# 6c.net
KiCad netlist of a schematic drawn in EAGLE
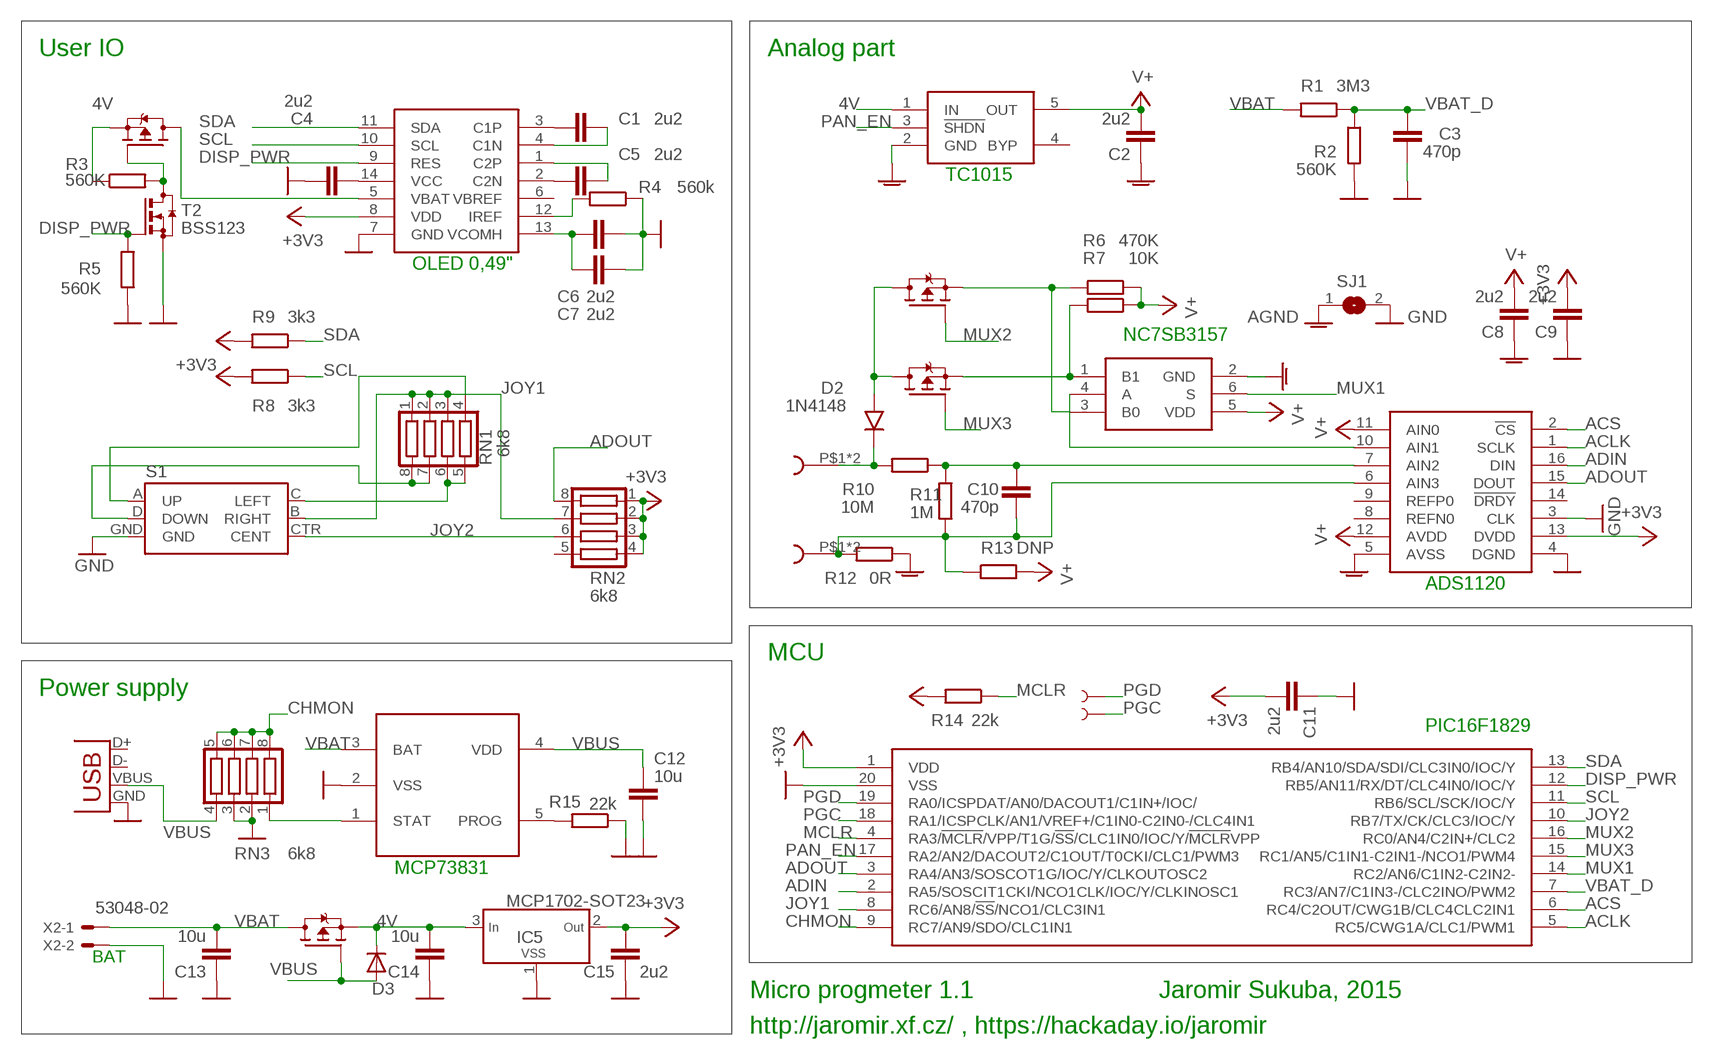
[diagram p0: schematic, sheet 1]

(export (version "E")
  (design (tool "Eeschema 10.0.6"))
  (components
    (comp (ref "C1")
      (value "2u2")
      (footprint "eagle-import:0603")
      (libsource (lib "eagle-import") (part "C_0603"))
    )
    (comp (ref "C2")
      (value "2u2")
      (footprint "eagle-import:0603")
      (libsource (lib "eagle-import") (part "C_0603"))
    )
    (comp (ref "C3")
      (value "470p")
      (footprint "eagle-import:0603")
      (libsource (lib "eagle-import") (part "C_0603"))
    )
    (comp (ref "C4")
      (value "2u2")
      (footprint "eagle-import:0603")
      (libsource (lib "eagle-import") (part "C_0603"))
    )
    (comp (ref "C5")
      (value "2u2")
      (footprint "eagle-import:0603")
      (libsource (lib "eagle-import") (part "C_0603"))
    )
    (comp (ref "C6")
      (value "2u2")
      (footprint "eagle-import:0603")
      (libsource (lib "eagle-import") (part "C_0603"))
    )
    (comp (ref "C7")
      (value "2u2")
      (footprint "eagle-import:0603")
      (libsource (lib "eagle-import") (part "C_0603"))
    )
    (comp (ref "C8")
      (value "2u2")
      (footprint "eagle-import:0603")
      (libsource (lib "eagle-import") (part "C_0603"))
    )
    (comp (ref "C9")
      (value "2u2")
      (footprint "eagle-import:0603")
      (libsource (lib "eagle-import") (part "C_0603"))
    )
    (comp (ref "C10")
      (value "470p")
      (footprint "eagle-import:0603")
      (libsource (lib "eagle-import") (part "C_0603"))
    )
    (comp (ref "C11")
      (value "2u2")
      (footprint "eagle-import:0603")
      (libsource (lib "eagle-import") (part "C_0603"))
    )
    (comp (ref "C12")
      (value "10u")
      (footprint "eagle-import:R0805")
      (libsource (lib "eagle-import") (part "C_0806"))
    )
    (comp (ref "C13")
      (value "10u")
      (footprint "eagle-import:R0805")
      (libsource (lib "eagle-import") (part "C_0806"))
    )
    (comp (ref "C14")
      (value "10u")
      (footprint "eagle-import:R0805")
      (libsource (lib "eagle-import") (part "C_0806"))
    )
    (comp (ref "C15")
      (value "2u2")
      (footprint "eagle-import:0603")
      (libsource (lib "eagle-import") (part "C_0603"))
    )
    (comp (ref "D1")
      (value "DISP_OLED_049B")
      (footprint "eagle-import:DISP_OLED_049_B")
      (libsource (lib "eagle-import") (part "DISP_OLED_049B"))
    )
    (comp (ref "D2")
      (value "1N4148")
      (footprint "eagle-import:SOD-80")
      (libsource (lib "eagle-import") (part "1N4148SOD"))
    )
    (comp (ref "D3")
      (value "DIODE-SOD123")
      (footprint "eagle-import:SOD123")
      (libsource (lib "eagle-import") (part "DIODE-SOD123"))
    )
    (comp (ref "IC1")
      (value "TC1015")
      (footprint "eagle-import:SOT23-5")
      (libsource (lib "eagle-import") (part "TC1015"))
    )
    (comp (ref "IC2")
      (value "NC7SB3157")
      (footprint "eagle-import:SC70-6")
      (libsource (lib "eagle-import") (part "NC7SB3157"))
    )
    (comp (ref "IC3")
      (value "ADS1120")
      (footprint "eagle-import:TSSOP16")
      (libsource (lib "eagle-import") (part "ADS1120"))
    )
    (comp (ref "IC4")
      (value "PIC16F1508SSOP20")
      (footprint "eagle-import:SSOP20")
      (libsource (lib "eagle-import") (part "PIC16F1508SSOP20"))
    )
    (comp (ref "IC5")
      (value "MCP1702-SOT23")
      (footprint "eagle-import:SOT23")
      (libsource (lib "eagle-import") (part "MCP1702-SOT23"))
    )
    (comp (ref "R1")
      (value "3M3")
      (footprint "eagle-import:0603")
      (libsource (lib "eagle-import") (part "R_0603"))
    )
    (comp (ref "R2")
      (value "560K")
      (footprint "eagle-import:0603")
      (libsource (lib "eagle-import") (part "R_0603"))
    )
    (comp (ref "R3")
      (value "560K")
      (footprint "eagle-import:0603")
      (libsource (lib "eagle-import") (part "R_0603"))
    )
    (comp (ref "R4")
      (value "560k")
      (footprint "eagle-import:0603")
      (libsource (lib "eagle-import") (part "R_0603"))
    )
    (comp (ref "R5")
      (value "560K")
      (footprint "eagle-import:0603")
      (libsource (lib "eagle-import") (part "R_0603"))
    )
    (comp (ref "R6")
      (value "470K")
      (footprint "eagle-import:R0805")
      (libsource (lib "eagle-import") (part "R_0805"))
    )
    (comp (ref "R7")
      (value "10K")
      (footprint "eagle-import:R0805")
      (libsource (lib "eagle-import") (part "R_0805"))
    )
    (comp (ref "R8")
      (value "3k3")
      (footprint "eagle-import:0603")
      (libsource (lib "eagle-import") (part "R_0603"))
    )
    (comp (ref "R9")
      (value "3k3")
      (footprint "eagle-import:0603")
      (libsource (lib "eagle-import") (part "R_0603"))
    )
    (comp (ref "R10")
      (value "10M")
      (footprint "eagle-import:R0805")
      (libsource (lib "eagle-import") (part "R_0805"))
    )
    (comp (ref "R11")
      (value "1M")
      (footprint "eagle-import:R0805")
      (libsource (lib "eagle-import") (part "R_0805"))
    )
    (comp (ref "R12")
      (value "0R")
      (footprint "eagle-import:0603")
      (libsource (lib "eagle-import") (part "R_0603"))
    )
    (comp (ref "R13")
      (value "DNP")
      (footprint "eagle-import:0603")
      (libsource (lib "eagle-import") (part "R_0603"))
    )
    (comp (ref "R14")
      (value "22k")
      (footprint "eagle-import:0603")
      (libsource (lib "eagle-import") (part "R_0603"))
    )
    (comp (ref "R15")
      (value "22k")
      (footprint "eagle-import:0603")
      (libsource (lib "eagle-import") (part "R_0603"))
    )
    (comp (ref "RN1")
      (value "6k8")
      (footprint "eagle-import:CTS742C083")
      (libsource (lib "eagle-import") (part "CTS742C083"))
    )
    (comp (ref "RN2")
      (value "6k8")
      (footprint "eagle-import:CTS742C083")
      (libsource (lib "eagle-import") (part "CTS742C083"))
    )
    (comp (ref "RN3")
      (value "6k8")
      (footprint "eagle-import:CTS742C083")
      (libsource (lib "eagle-import") (part "CTS742C083"))
    )
    (comp (ref "S1")
      (value "JOYSTICK_MINI")
      (footprint "eagle-import:JOYSTICK_MINI")
      (libsource (lib "eagle-import") (part "JOYSTICK_MINI"))
    )
    (comp (ref "SJ1") (value "SJ") (footprint "eagle-import:SJ") (libsource (lib "eagle-import") (part "SJ")))
    (comp (ref "T1")
      (value "BSS84")
      (footprint "eagle-import:SOT23-3")
      (libsource (lib "eagle-import") (part "BSS84"))
    )
    (comp (ref "T2")
      (value "BSS123")
      (footprint "eagle-import:SOT23")
      (libsource (lib "eagle-import") (part "BSS123"))
    )
    (comp (ref "T3")
      (value "BSS84")
      (footprint "eagle-import:SOT23-3")
      (libsource (lib "eagle-import") (part "BSS84"))
    )
    (comp (ref "T4")
      (value "BSS84")
      (footprint "eagle-import:SOT23-3")
      (libsource (lib "eagle-import") (part "BSS84"))
    )
    (comp (ref "T5")
      (value "BSS84")
      (footprint "eagle-import:SOT23-3")
      (libsource (lib "eagle-import") (part "BSS84"))
    )
    (comp (ref "TP1")
      (value "TEST-POINT3X5")
      (footprint "eagle-import:PAD.03X.05")
      (libsource (lib "eagle-import") (part "TEST-POINT3X5"))
    )
    (comp (ref "TP2")
      (value "TEST-POINT3X5")
      (footprint "eagle-import:PAD.03X.05")
      (libsource (lib "eagle-import") (part "TEST-POINT3X5"))
    )
    (comp (ref "U$1")
      (value "BANPLUG_2")
      (footprint "eagle-import:BANPLUG_2")
      (libsource (lib "eagle-import") (part "BANPLUG_2"))
    )
    (comp (ref "U$2")
      (value "BANPLUG_2")
      (footprint "eagle-import:BANPLUG_2")
      (libsource (lib "eagle-import") (part "BANPLUG_2"))
    )
    (comp (ref "U$3")
      (value "MCP73831")
      (footprint "eagle-import:SOT23-5")
      (libsource (lib "eagle-import") (part "MCP73831"))
    )
    (comp (ref "X1")
      (value "USB-MICROB")
      (footprint "eagle-import:USB-MICROB")
      (libsource (lib "eagle-import") (part "USB-MICROB"))
    )
    (comp (ref "X2")
      (value "53048-02")
      (footprint "eagle-import:53048-02")
      (libsource (lib "eagle-import") (part "53?-02048"))
    )
  )
  (nets
    (net (code "1") (name "+3V3") (class "Default")
      (node (ref "C11") (pin "2") (pinfunction "2_2") (pintype "passive"))
      (node (ref "C15") (pin "2") (pinfunction "2_2") (pintype "passive"))
      (node (ref "C9") (pin "2") (pinfunction "2_2") (pintype "passive"))
      (node (ref "D1") (pin "8") (pinfunction "VDD_8") (pintype "bidirectional"))
      (node (ref "IC3") (pin "13") (pinfunction "DVDD_13") (pintype "bidirectional"))
      (node (ref "IC4") (pin "1") (pinfunction "VDD_1") (pintype "bidirectional"))
      (node (ref "IC5") (pin "2") (pinfunction "OUT_2") (pintype "output"))
      (node (ref "R14") (pin "2") (pinfunction "2_2") (pintype "passive"))
      (node (ref "R8") (pin "2") (pinfunction "2_2") (pintype "passive"))
      (node (ref "R9") (pin "2") (pinfunction "2_2") (pintype "passive"))
      (node (ref "RN2") (pin "1") (pinfunction "1_1") (pintype "passive"))
      (node (ref "RN2") (pin "2") (pinfunction "2_2") (pintype "passive"))
      (node (ref "RN2") (pin "3") (pinfunction "3_3") (pintype "passive"))
      (node (ref "RN2") (pin "4") (pinfunction "4_4") (pintype "passive"))
    )
    (net (code "2") (name "/4V") (class "Default")
      (node (ref "C14") (pin "2") (pinfunction "2_2") (pintype "passive"))
      (node (ref "D3") (pin "C") (pinfunction "C_C") (pintype "passive"))
      (node (ref "IC1") (pin "1") (pinfunction "IN_1") (pintype "bidirectional"))
      (node (ref "IC5") (pin "3") (pinfunction "IN_3") (pintype "input"))
      (node (ref "R3") (pin "1") (pinfunction "1_1") (pintype "passive"))
      (node (ref "T1") (pin "2") (pinfunction "S_2") (pintype "passive"))
      (node (ref "T5") (pin "2") (pinfunction "S_2") (pintype "passive"))
    )
    (net (code "3") (name "/ACLK") (class "Default")
      (node (ref "IC3") (pin "1") (pinfunction "SCLK_1") (pintype "bidirectional"))
      (node (ref "IC4") (pin "5") (pinfunction "RC5/CWG1A/CLC1/PWM1_5") (pintype "bidirectional"))
    )
    (net (code "4") (name "/ACS") (class "Default")
      (node (ref "IC3") (pin "2") (pinfunction "~{CS}_2") (pintype "bidirectional"))
      (node (ref "IC4") (pin "6") (pinfunction "RC4/C2OUT/CWG1B/CLC4CLC2IN1_6") (pintype "bidirectional"))
    )
    (net (code "5") (name "/ADIN") (class "Default")
      (node (ref "IC3") (pin "16") (pinfunction "DIN_16") (pintype "bidirectional"))
      (node (ref "IC4") (pin "2") (pinfunction "RA5/SOSCIT1CKI/NCO1CLK/IOC/Y/CLKINOSC1_2") (pintype "bidirectional"))
    )
    (net (code "6") (name "/ADOUT") (class "Default")
      (node (ref "IC3") (pin "15") (pinfunction "DOUT_15") (pintype "bidirectional"))
      (node (ref "IC4") (pin "3") (pinfunction "RA4/AN3/SOSCOT1G/IOC/Y/CLKOUTOSC2_3") (pintype "bidirectional"))
      (node (ref "RN2") (pin "8") (pinfunction "8_8") (pintype "passive"))
    )
    (net (code "7") (name "/CHMON") (class "Default")
      (node (ref "IC4") (pin "9") (pinfunction "RC7/AN9/SDO/CLC1IN1_9") (pintype "bidirectional"))
      (node (ref "RN3") (pin "5") (pinfunction "5_5") (pintype "passive"))
      (node (ref "RN3") (pin "6") (pinfunction "6_6") (pintype "passive"))
      (node (ref "RN3") (pin "7") (pinfunction "7_7") (pintype "passive"))
      (node (ref "RN3") (pin "8") (pinfunction "8_8") (pintype "passive"))
    )
    (net (code "8") (name "/DISP_PWR") (class "Default")
      (node (ref "D1") (pin "9") (pinfunction "RES_9") (pintype "bidirectional"))
      (node (ref "IC4") (pin "12") (pinfunction "RB5/AN11/RX/DT/CLC4IN0/IOC/Y_12") (pintype "bidirectional"))
      (node (ref "R5") (pin "2") (pinfunction "2_2") (pintype "passive"))
      (node (ref "T2") (pin "1") (pinfunction "G_1") (pintype "passive"))
    )
    (net (code "9") (name "/JOY1") (class "Default")
      (node (ref "IC4") (pin "8") (pinfunction "RC6/AN8/~{SS}/NCO1/CLC3IN1_8") (pintype "bidirectional"))
      (node (ref "RN1") (pin "1") (pinfunction "1_1") (pintype "passive"))
      (node (ref "RN1") (pin "2") (pinfunction "2_2") (pintype "passive"))
      (node (ref "RN1") (pin "3") (pinfunction "3_3") (pintype "passive"))
      (node (ref "RN2") (pin "7") (pinfunction "7_7") (pintype "passive"))
      (node (ref "S1") (pin "B") (pinfunction "RIGHT_B") (pintype "bidirectional"))
    )
    (net (code "10") (name "/JOY2") (class "Default")
      (node (ref "IC4") (pin "10") (pinfunction "RB7/TX/CK/CLC3/IOC/Y_10") (pintype "bidirectional"))
      (node (ref "RN2") (pin "6") (pinfunction "6_6") (pintype "passive"))
      (node (ref "S1") (pin "CTR") (pinfunction "CENT_CTR") (pintype "bidirectional"))
    )
    (net (code "11") (name "/MCLR") (class "Default")
      (node (ref "IC4") (pin "4") (pinfunction "RA3/~{MCLR}/VPP/T1G/~{SS}/CLC1IN0/IOC/Y/~{MCLR}VPP_4") (pintype "bidirectional"))
      (node (ref "R14") (pin "1") (pinfunction "1_1") (pintype "passive"))
    )
    (net (code "12") (name "/MUX1") (class "Default")
      (node (ref "IC2") (pin "6") (pinfunction "S_6") (pintype "bidirectional"))
      (node (ref "IC4") (pin "14") (pinfunction "RC2/AN6/C1IN2-C2IN2-_14") (pintype "bidirectional"))
    )
    (net (code "13") (name "/MUX2") (class "Default")
      (node (ref "IC4") (pin "16") (pinfunction "RC0/AN4/C2IN+/CLC2_16") (pintype "bidirectional"))
      (node (ref "T3") (pin "1") (pinfunction "G_1") (pintype "passive"))
    )
    (net (code "14") (name "/MUX3") (class "Default")
      (node (ref "IC4") (pin "15") (pinfunction "RC1/AN5/C1IN1-C2IN1-/NCO1/PWM4_15") (pintype "bidirectional"))
      (node (ref "T4") (pin "1") (pinfunction "G_1") (pintype "passive"))
    )
    (net (code "15") (name "/PAN_EN") (class "Default")
      (node (ref "IC1") (pin "3") (pinfunction "~{SHDN}_3") (pintype "bidirectional"))
      (node (ref "IC4") (pin "17") (pinfunction "RA2/AN2/DACOUT2/C1OUT/T0CKI/CLC1/PWM3_17") (pintype "bidirectional"))
    )
    (net (code "16") (name "/PGC") (class "Default")
      (node (ref "IC4") (pin "18") (pinfunction "RA1/ICSPCLK/AN1/VREF+/C1IN0-C2IN0-/CLC4IN1_18") (pintype "bidirectional"))
      (node (ref "TP2") (pin "P$1") (pinfunction "1_P$1") (pintype "bidirectional"))
    )
    (net (code "17") (name "/PGD") (class "Default")
      (node (ref "IC4") (pin "19") (pinfunction "RA0/ICSPDAT/AN0/DACOUT1/C1IN+/IOC/_19") (pintype "bidirectional"))
      (node (ref "TP1") (pin "P$1") (pinfunction "1_P$1") (pintype "bidirectional"))
    )
    (net (code "18") (name "/SCL") (class "Default")
      (node (ref "D1") (pin "10") (pinfunction "SCL_10") (pintype "bidirectional"))
      (node (ref "IC4") (pin "11") (pinfunction "RB6/SCL/SCK/IOC/Y_11") (pintype "bidirectional"))
      (node (ref "R9") (pin "1") (pinfunction "1_1") (pintype "passive"))
    )
    (net (code "19") (name "/SDA") (class "Default")
      (node (ref "D1") (pin "11") (pinfunction "SDA_11") (pintype "bidirectional"))
      (node (ref "IC4") (pin "13") (pinfunction "RB4/AN10/SDA/SDI/CLC3IN0/IOC/Y_13") (pintype "bidirectional"))
      (node (ref "R8") (pin "1") (pinfunction "1_1") (pintype "passive"))
    )
    (net (code "20") (name "/VBAT") (class "Default")
      (node (ref "C13") (pin "2") (pinfunction "2_2") (pintype "passive"))
      (node (ref "R1") (pin "2") (pinfunction "2_2") (pintype "passive"))
      (node (ref "T5") (pin "3") (pinfunction "D_3") (pintype "passive"))
      (node (ref "U$3") (pin "3") (pinfunction "BAT_3") (pintype "bidirectional"))
      (node (ref "X2") (pin "1") (pinfunction "S_1") (pintype "passive"))
    )
    (net (code "21") (name "/VBAT_D") (class "Default")
      (node (ref "C3") (pin "2") (pinfunction "2_2") (pintype "passive"))
      (node (ref "IC4") (pin "7") (pinfunction "RC3/AN7/C1IN3-/CLC2INO/PWM2_7") (pintype "bidirectional"))
      (node (ref "R1") (pin "1") (pinfunction "1_1") (pintype "passive"))
      (node (ref "R2") (pin "1") (pinfunction "1_1") (pintype "passive"))
    )
    (net (code "22") (name "/VBUS") (class "Default")
      (node (ref "C12") (pin "1") (pinfunction "1_1") (pintype "passive"))
      (node (ref "D3") (pin "A") (pinfunction "A_A") (pintype "passive"))
      (node (ref "RN3") (pin "4") (pinfunction "4_4") (pintype "passive"))
      (node (ref "T5") (pin "1") (pinfunction "G_1") (pintype "passive"))
      (node (ref "U$3") (pin "4") (pinfunction "VDD_4") (pintype "bidirectional"))
      (node (ref "X1") (pin "VBUS") (pinfunction "VBUS_VBUS") (pintype "bidirectional"))
    )
    (net (code "23") (name "AGND") (class "Default")
      (node (ref "C2") (pin "1") (pinfunction "1_1") (pintype "passive"))
      (node (ref "C8") (pin "1") (pinfunction "1_1") (pintype "passive"))
      (node (ref "IC1") (pin "2") (pinfunction "GND_2") (pintype "bidirectional"))
      (node (ref "IC2") (pin "2") (pinfunction "GND_2") (pintype "bidirectional"))
      (node (ref "IC3") (pin "5") (pinfunction "AVSS_5") (pintype "bidirectional"))
      (node (ref "R12") (pin "1") (pinfunction "1_1") (pintype "passive"))
      (node (ref "SJ1") (pin "1") (pinfunction "1_1") (pintype "passive"))
    )
    (net (code "24") (name "GND") (class "Default")
      (node (ref "C11") (pin "1") (pinfunction "1_1") (pintype "passive"))
      (node (ref "C12") (pin "2") (pinfunction "2_2") (pintype "passive"))
      (node (ref "C13") (pin "1") (pinfunction "1_1") (pintype "passive"))
      (node (ref "C14") (pin "1") (pinfunction "1_1") (pintype "passive"))
      (node (ref "C15") (pin "1") (pinfunction "1_1") (pintype "passive"))
      (node (ref "C3") (pin "1") (pinfunction "1_1") (pintype "passive"))
      (node (ref "C4") (pin "1") (pinfunction "1_1") (pintype "passive"))
      (node (ref "C6") (pin "2") (pinfunction "2_2") (pintype "passive"))
      (node (ref "C7") (pin "2") (pinfunction "2_2") (pintype "passive"))
      (node (ref "C9") (pin "1") (pinfunction "1_1") (pintype "passive"))
      (node (ref "D1") (pin "7") (pinfunction "GND_7") (pintype "bidirectional"))
      (node (ref "IC3") (pin "3") (pinfunction "CLK_3") (pintype "bidirectional"))
      (node (ref "IC3") (pin "4") (pinfunction "DGND_4") (pintype "bidirectional"))
      (node (ref "IC4") (pin "20") (pinfunction "VSS_20") (pintype "bidirectional"))
      (node (ref "IC5") (pin "1") (pinfunction "VSS_1") (pintype "input"))
      (node (ref "R15") (pin "1") (pinfunction "1_1") (pintype "passive"))
      (node (ref "R2") (pin "2") (pinfunction "2_2") (pintype "passive"))
      (node (ref "R4") (pin "1") (pinfunction "1_1") (pintype "passive"))
      (node (ref "R5") (pin "1") (pinfunction "1_1") (pintype "passive"))
      (node (ref "RN3") (pin "2") (pinfunction "2_2") (pintype "passive"))
      (node (ref "RN3") (pin "3") (pinfunction "3_3") (pintype "passive"))
      (node (ref "S1") (pin "GND") (pinfunction "GND_GND") (pintype "bidirectional"))
      (node (ref "SJ1") (pin "2") (pinfunction "2_2") (pintype "passive"))
      (node (ref "T2") (pin "2") (pinfunction "S_2") (pintype "passive"))
      (node (ref "U$3") (pin "2") (pinfunction "VSS_2") (pintype "bidirectional"))
      (node (ref "X1") (pin "GND") (pinfunction "GND_GND") (pintype "bidirectional"))
      (node (ref "X2") (pin "2") (pinfunction "S_2") (pintype "passive"))
    )
    (net (code "25") (name "Net-(D1-C1N)") (class "Default")
      (node (ref "C1") (pin "2") (pinfunction "2_2") (pintype "passive"))
      (node (ref "D1") (pin "4") (pinfunction "C1N_4") (pintype "bidirectional"))
    )
    (net (code "26") (name "Net-(D1-C1P)") (class "Default")
      (node (ref "C1") (pin "1") (pinfunction "1_1") (pintype "passive"))
      (node (ref "D1") (pin "3") (pinfunction "C1P_3") (pintype "bidirectional"))
    )
    (net (code "27") (name "Net-(D1-C2N)") (class "Default")
      (node (ref "C5") (pin "1") (pinfunction "1_1") (pintype "passive"))
      (node (ref "D1") (pin "2") (pinfunction "C2N_2") (pintype "bidirectional"))
    )
    (net (code "28") (name "Net-(D1-C2P)") (class "Default")
      (node (ref "C5") (pin "2") (pinfunction "2_2") (pintype "passive"))
      (node (ref "D1") (pin "1") (pinfunction "C2P_1") (pintype "bidirectional"))
    )
    (net (code "29") (name "Net-(D1-IREF)") (class "Default")
      (node (ref "D1") (pin "12") (pinfunction "IREF_12") (pintype "bidirectional"))
      (node (ref "R4") (pin "2") (pinfunction "2_2") (pintype "passive"))
    )
    (net (code "30") (name "Net-(D1-VBAT)") (class "Default")
      (node (ref "D1") (pin "5") (pinfunction "VBAT_5") (pintype "bidirectional"))
      (node (ref "T1") (pin "3") (pinfunction "D_3") (pintype "passive"))
    )
    (net (code "31") (name "Net-(D1-VCC)") (class "Default")
      (node (ref "C4") (pin "2") (pinfunction "2_2") (pintype "passive"))
      (node (ref "D1") (pin "14") (pinfunction "VCC_14") (pintype "bidirectional"))
    )
    (net (code "32") (name "Net-(D1-VCOMH)") (class "Default")
      (node (ref "C6") (pin "1") (pinfunction "1_1") (pintype "passive"))
      (node (ref "C7") (pin "1") (pinfunction "1_1") (pintype "passive"))
      (node (ref "D1") (pin "13") (pinfunction "VCOMH_13") (pintype "bidirectional"))
    )
    (net (code "33") (name "Net-(D2-PadK)") (class "Default")
      (node (ref "D2") (pin "K") (pinfunction "K_K") (pintype "output"))
      (node (ref "R10") (pin "2") (pinfunction "2_2") (pintype "passive"))
      (node (ref "U$1") (pin "P$1") (pinfunction "P$1_P$1") (pintype "bidirectional"))
      (node (ref "U$1") (pin "P$2") (pinfunction "P$1_P$2") (pintype "bidirectional"))
    )
    (net (code "34") (name "Net-(IC2-A)") (class "Default")
      (node (ref "IC2") (pin "4") (pinfunction "A_4") (pintype "bidirectional"))
      (node (ref "IC3") (pin "10") (pinfunction "AIN1_10") (pintype "bidirectional"))
    )
    (net (code "35") (name "Net-(IC2-B0)") (class "Default")
      (node (ref "IC2") (pin "3") (pinfunction "B0_3") (pintype "bidirectional"))
      (node (ref "R6") (pin "2") (pinfunction "2_2") (pintype "passive"))
      (node (ref "T3") (pin "2") (pinfunction "S_2") (pintype "passive"))
    )
    (net (code "36") (name "Net-(IC2-B1)") (class "Default")
      (node (ref "IC2") (pin "1") (pinfunction "B1_1") (pintype "bidirectional"))
      (node (ref "R7") (pin "2") (pinfunction "2_2") (pintype "passive"))
      (node (ref "T4") (pin "2") (pinfunction "S_2") (pintype "passive"))
    )
    (net (code "37") (name "Net-(IC3-AIN2)") (class "Default")
      (node (ref "C10") (pin "2") (pinfunction "2_2") (pintype "passive"))
      (node (ref "IC3") (pin "7") (pinfunction "AIN2_7") (pintype "bidirectional"))
      (node (ref "R10") (pin "1") (pinfunction "1_1") (pintype "passive"))
      (node (ref "R11") (pin "1") (pinfunction "1_1") (pintype "passive"))
    )
    (net (code "38") (name "Net-(IC3-AIN3)") (class "Default")
      (node (ref "C10") (pin "1") (pinfunction "1_1") (pintype "passive"))
      (node (ref "IC3") (pin "6") (pinfunction "AIN3_6") (pintype "bidirectional"))
      (node (ref "R11") (pin "2") (pinfunction "2_2") (pintype "passive"))
      (node (ref "R12") (pin "2") (pinfunction "2_2") (pintype "passive"))
      (node (ref "R13") (pin "1") (pinfunction "1_1") (pintype "passive"))
      (node (ref "U$2") (pin "P$1") (pinfunction "P$1_P$1") (pintype "bidirectional"))
      (node (ref "U$2") (pin "P$2") (pinfunction "P$1_P$2") (pintype "bidirectional"))
    )
    (net (code "39") (name "Net-(S1-DOWN)") (class "Default")
      (node (ref "RN1") (pin "7") (pinfunction "7_7") (pintype "passive"))
      (node (ref "RN1") (pin "8") (pinfunction "8_8") (pintype "passive"))
      (node (ref "S1") (pin "D") (pinfunction "DOWN_D") (pintype "bidirectional"))
    )
    (net (code "40") (name "Net-(S1-LEFT)") (class "Default")
      (node (ref "RN1") (pin "5") (pinfunction "5_5") (pintype "passive"))
      (node (ref "RN1") (pin "6") (pinfunction "6_6") (pintype "passive"))
      (node (ref "S1") (pin "C") (pinfunction "LEFT_C") (pintype "bidirectional"))
    )
    (net (code "41") (name "Net-(S1-UP)") (class "Default")
      (node (ref "RN1") (pin "4") (pinfunction "4_4") (pintype "passive"))
      (node (ref "S1") (pin "A") (pinfunction "UP_A") (pintype "bidirectional"))
    )
    (net (code "42") (name "Net-(T1-G)") (class "Default")
      (node (ref "R3") (pin "2") (pinfunction "2_2") (pintype "passive"))
      (node (ref "T1") (pin "1") (pinfunction "G_1") (pintype "passive"))
      (node (ref "T2") (pin "3") (pinfunction "D_3") (pintype "passive"))
    )
    (net (code "43") (name "Net-(T3-D)") (class "Default")
      (node (ref "D2") (pin "A") (pinfunction "A_A") (pintype "input"))
      (node (ref "T3") (pin "3") (pinfunction "D_3") (pintype "passive"))
      (node (ref "T4") (pin "3") (pinfunction "D_3") (pintype "passive"))
    )
    (net (code "44") (name "Net-(U$3-PROG)") (class "Default")
      (node (ref "R15") (pin "2") (pinfunction "2_2") (pintype "passive"))
      (node (ref "U$3") (pin "5") (pinfunction "PROG_5") (pintype "bidirectional"))
    )
    (net (code "45") (name "Net-(U$3-STAT)") (class "Default")
      (node (ref "RN3") (pin "1") (pinfunction "1_1") (pintype "passive"))
      (node (ref "U$3") (pin "1") (pinfunction "STAT_1") (pintype "bidirectional"))
    )
    (net (code "46") (name "V+") (class "Default")
      (node (ref "C2") (pin "2") (pinfunction "2_2") (pintype "passive"))
      (node (ref "C8") (pin "2") (pinfunction "2_2") (pintype "passive"))
      (node (ref "IC1") (pin "5") (pinfunction "OUT_5") (pintype "bidirectional"))
      (node (ref "IC2") (pin "5") (pinfunction "VDD_5") (pintype "bidirectional"))
      (node (ref "IC3") (pin "11") (pinfunction "AIN0_11") (pintype "bidirectional"))
      (node (ref "IC3") (pin "12") (pinfunction "AVDD_12") (pintype "bidirectional"))
      (node (ref "R13") (pin "2") (pinfunction "2_2") (pintype "passive"))
      (node (ref "R6") (pin "1") (pinfunction "1_1") (pintype "passive"))
      (node (ref "R7") (pin "1") (pinfunction "1_1") (pintype "passive"))
    )
    (net (code "47") (name "unconnected-(D1-VBREF-Pad6)") (class "Default")
      (node (ref "D1") (pin "6") (pinfunction "VBREF_6") (pintype "bidirectional"))
    )
    (net (code "48") (name "unconnected-(IC1-BYP-Pad4)") (class "Default")
      (node (ref "IC1") (pin "4") (pinfunction "BYP_4") (pintype "bidirectional"))
    )
    (net (code "49") (name "unconnected-(IC3-REFN0-Pad8)") (class "Default")
      (node (ref "IC3") (pin "8") (pinfunction "REFN0_8") (pintype "bidirectional"))
    )
    (net (code "50") (name "unconnected-(IC3-REFP0-Pad9)") (class "Default")
      (node (ref "IC3") (pin "9") (pinfunction "REFP0_9") (pintype "bidirectional"))
    )
    (net (code "51") (name "unconnected-(IC3-~{DRDY}-Pad14)") (class "Default")
      (node (ref "IC3") (pin "14") (pinfunction "~{DRDY}_14") (pintype "bidirectional"))
    )
    (net (code "52") (name "unconnected-(RN2-Pad5)") (class "Default")
      (node (ref "RN2") (pin "5") (pinfunction "5_5") (pintype "passive"))
    )
    (net (code "53") (name "unconnected-(X1-PadD+)") (class "Default")
      (node (ref "X1") (pin "D+") (pinfunction "D+_D+") (pintype "bidirectional"))
    )
    (net (code "54") (name "unconnected-(X1-PadD-)") (class "Default")
      (node (ref "X1") (pin "D-") (pinfunction "D-_D-") (pintype "bidirectional"))
    )
  )
)
